# AIRZAI_LED_SENSE_FLEX_REVA.net
KiCad netlist of a schematic drawn in Altium Designer
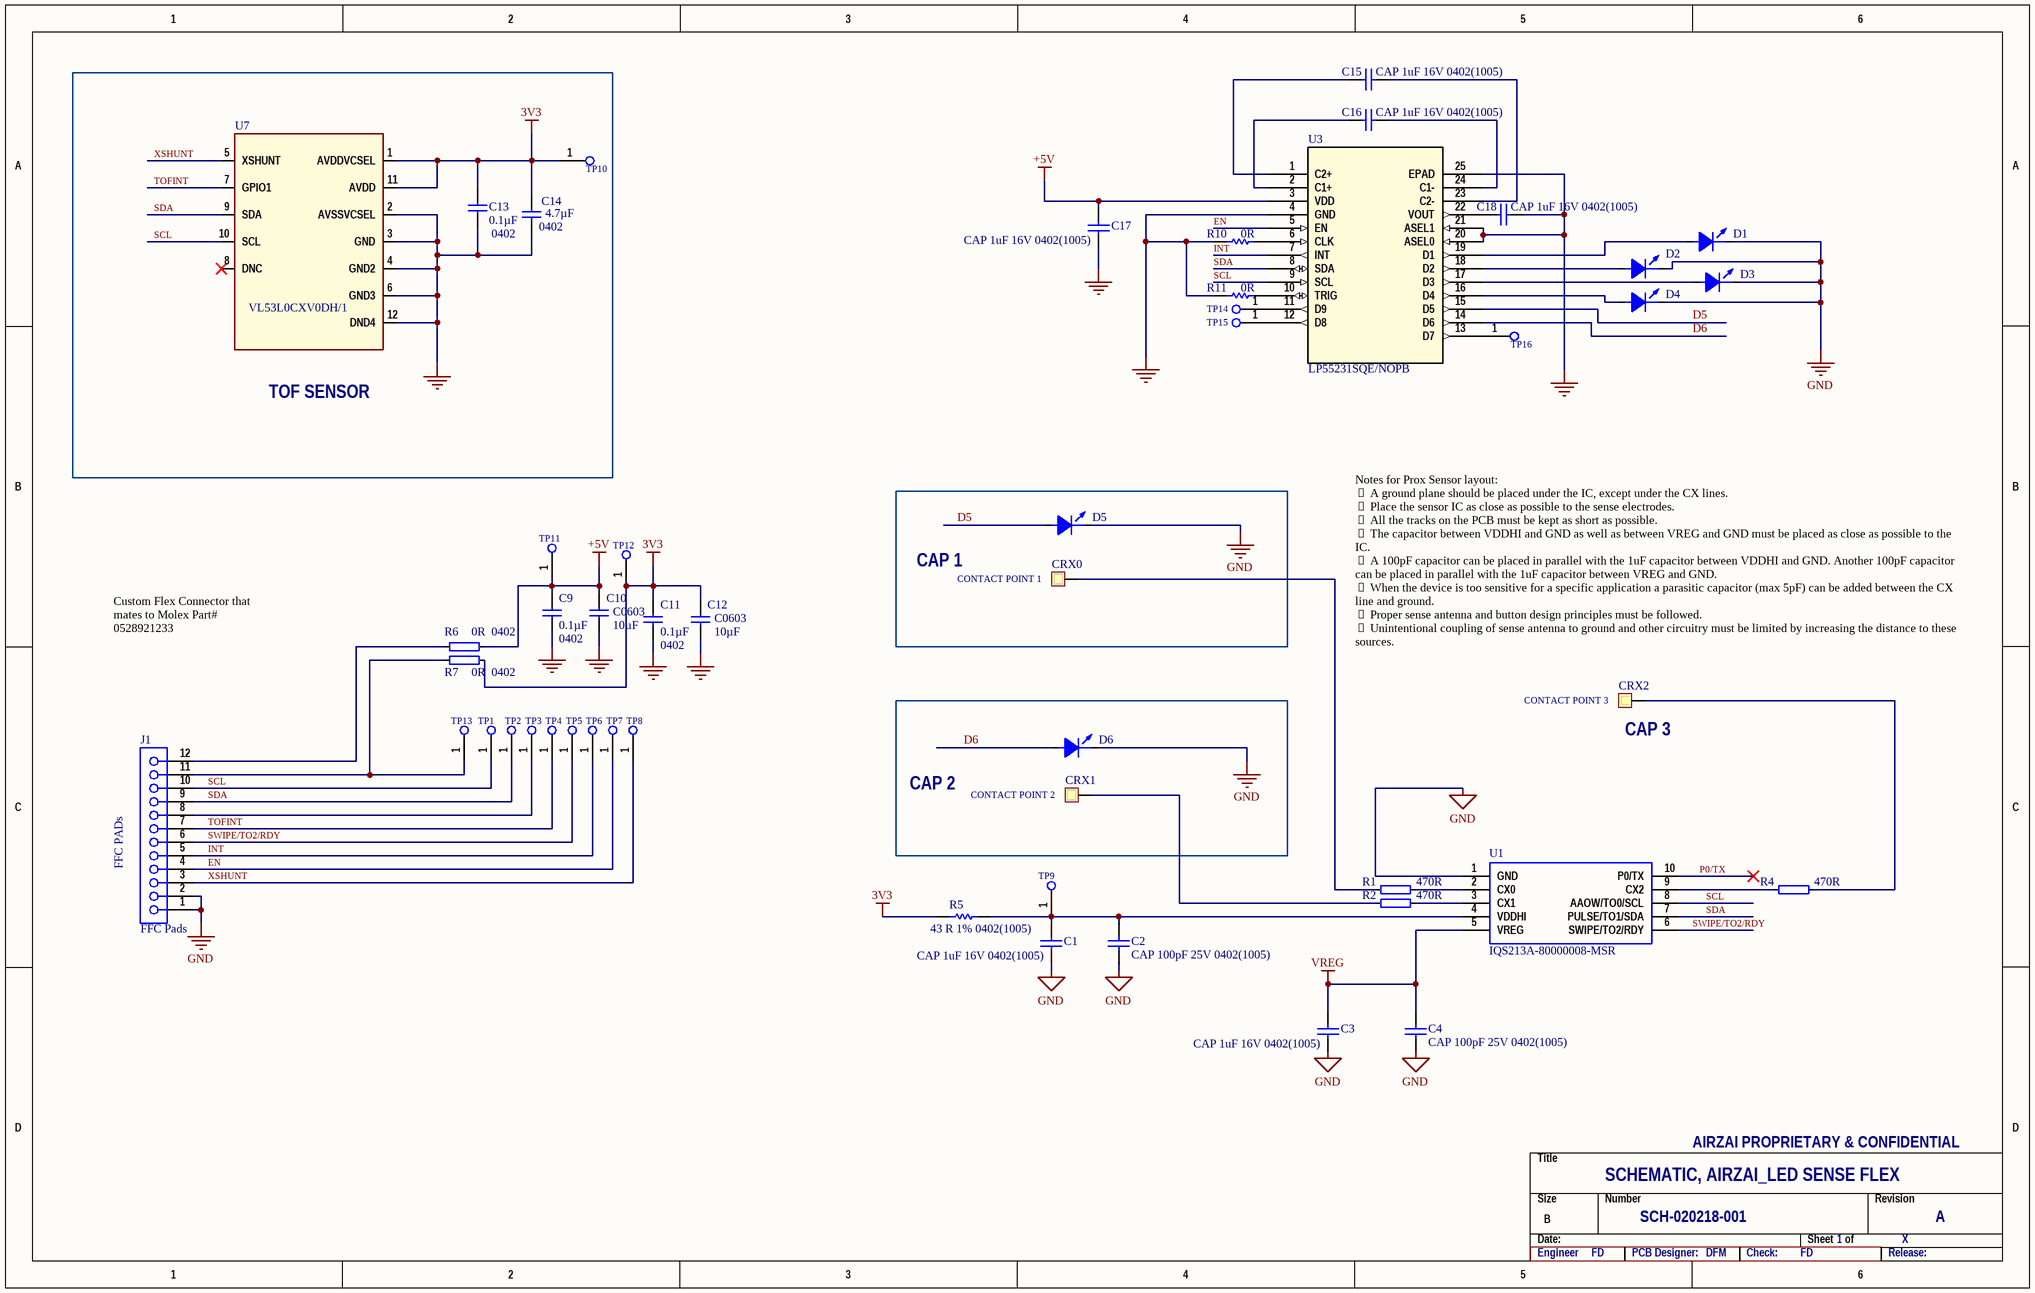
[diagram p0: AIRZAI_LED_SENSE_FLEX_REVA.SchDoc]

(export (version "E")
  (design (tool "Eeschema 10.0.6"))
  (components
    (comp (ref "C1")
      (value "CAP 1uF 16V 0402(1005)")
      (footprint "0402-A")
      (description "CAP 1uF 16V ±10% 0402 (1005 Metric) Thickness 0.6mm SMD")
      (fields (field (name "TOLERANCE") "Â±10%") (field (name "MANUFACTURER") "Taiyo Yuden"))
      (libsource (lib "AIRZAI_LED_SENSE_FLEX_REVA") (part "CAP"))
    )
    (comp (ref "C2")
      (value "CAP 100pF 25V 0402(1005)")
      (footprint "0402-A")
      (description "CAP 100pF 25V ±2% 0402 (1005 Metric) Thickness 0.6mm SMD")
      (fields (field (name "TOLERANCE") "Â±2%") (field (name "MANUFACTURER") "Yageo"))
      (libsource (lib "AIRZAI_LED_SENSE_FLEX_REVA") (part "CAP"))
    )
    (comp (ref "C3")
      (value "CAP 1uF 16V 0402(1005)")
      (footprint "0402-A")
      (description "CAP 1uF 16V ±10% 0402 (1005 Metric) Thickness 0.6mm SMD")
      (fields (field (name "TOLERANCE") "Â±10%") (field (name "MANUFACTURER") "Taiyo Yuden"))
      (libsource (lib "AIRZAI_LED_SENSE_FLEX_REVA") (part "CAP"))
    )
    (comp (ref "C4")
      (value "CAP 100pF 25V 0402(1005)")
      (footprint "0402-A")
      (description "CAP 100pF 25V ±2% 0402 (1005 Metric) Thickness 0.6mm SMD")
      (fields (field (name "TOLERANCE") "Â±2%") (field (name "MANUFACTURER") "Yageo"))
      (libsource (lib "AIRZAI_LED_SENSE_FLEX_REVA") (part "CAP"))
    )
    (comp (ref "C9")
      (value "0.1µF")
      (footprint "0402")
      (description "Capacitor, X7R, ±10%")
      (fields (field (name "MANUFACTURER") "TDK") (field (name "MANUFACTURER PART NUMBER") "C1005X7R1C104K"))
      (libsource (lib "Nordic Passive DB") (part "CAP"))
    )
    (comp (ref "C10")
      (value "10µF")
      (footprint "C0603")
      (description "Capacitor, X7R, ±10%")
      (fields
        (field (name "MANUFACTURER") "MURATA")
        (field (name "MANUFACTURER PART NUMBER") "GRM188R60J106ME47D")
      )
      (libsource (lib "Nordic Passive DB") (part "CAP"))
    )
    (comp (ref "C11")
      (value "0.1µF")
      (footprint "0402")
      (description "Capacitor, X7R, ±10%")
      (fields (field (name "MANUFACTURER") "TDK") (field (name "MANUFACTURER PART NUMBER") "C1005X7R1C104K"))
      (libsource (lib "Nordic Passive DB") (part "CAP"))
    )
    (comp (ref "C12")
      (value "10µF")
      (footprint "C0603")
      (description "Capacitor, X7R, ±10%")
      (fields
        (field (name "MANUFACTURER") "MURATA")
        (field (name "MANUFACTURER PART NUMBER") "GRM188R60J106ME47D")
      )
      (libsource (lib "Nordic Passive DB") (part "CAP"))
    )
    (comp (ref "C13")
      (value "0.1µF")
      (footprint "0402")
      (description "Capacitor, X7R, ±10%")
      (fields (field (name "MANUFACTURER") "TDK") (field (name "MANUFACTURER PART NUMBER") "C1005X7R1C104K"))
      (libsource (lib "Nordic Passive DB") (part "CAP"))
    )
    (comp (ref "C14")
      (value "4.7µF")
      (footprint "0402")
      (description "Capacitor, X7R, ±10%")
      (fields (field (name "MANUFACTURER") "TDK") (field (name "MANUFACTURER PART NUMBER") "C1005X5R0J475M"))
      (libsource (lib "Nordic Passive DB") (part "CAP"))
    )
    (comp (ref "C15")
      (value "CAP 1uF 16V 0402(1005)")
      (footprint "CAPC0402(1005)60_M")
      (description "CAP 1uF 16V ±10% 0402 (1005 Metric) Thickness 0.6mm SMD")
      (fields (field (name "TOLERANCE") "Â±10%") (field (name "MANUFACTURER") "Taiyo Yuden"))
      (libsource (lib "AIRZAI_LED_SENSE_FLEX_REVA") (part "CAP"))
    )
    (comp (ref "C16")
      (value "CAP 1uF 16V 0402(1005)")
      (footprint "CAPC0402(1005)60_M")
      (description "CAP 1uF 16V ±10% 0402 (1005 Metric) Thickness 0.6mm SMD")
      (fields (field (name "TOLERANCE") "Â±10%") (field (name "MANUFACTURER") "Taiyo Yuden"))
      (libsource (lib "AIRZAI_LED_SENSE_FLEX_REVA") (part "CAP"))
    )
    (comp (ref "C17")
      (value "CAP 1uF 16V 0402(1005)")
      (footprint "CAPC0402(1005)60_M")
      (description "CAP 1uF 16V ±10% 0402 (1005 Metric) Thickness 0.6mm SMD")
      (fields (field (name "TOLERANCE") "Â±10%") (field (name "MANUFACTURER") "Taiyo Yuden"))
      (libsource (lib "AIRZAI_LED_SENSE_FLEX_REVA") (part "CAP"))
    )
    (comp (ref "C18")
      (value "CAP 1uF 16V 0402(1005)")
      (footprint "CAPC0402(1005)60_M")
      (description "CAP 1uF 16V ±10% 0402 (1005 Metric) Thickness 0.6mm SMD")
      (fields (field (name "TOLERANCE") "Â±10%") (field (name "MANUFACTURER") "Taiyo Yuden"))
      (libsource (lib "AIRZAI_LED_SENSE_FLEX_REVA") (part "CAP"))
    )
    (comp (ref "CRX0")
      (value "CONTACT POINT 1")
      (footprint "CONTACT_POINT_1CM _SQ")
      (libsource (lib "AIRZAI_LED_SENSE_FLEX_REVA") (part "WIRE_POINT"))
    )
    (comp (ref "CRX1")
      (value "CONTACT POINT 2")
      (footprint "CONTACT_POINT_1CM _SQ")
      (libsource (lib "AIRZAI_LED_SENSE_FLEX_REVA") (part "WIRE_POINT"))
    )
    (comp (ref "CRX2")
      (value "CONTACT POINT 3")
      (footprint "CONTACT_POINT_0.7CM")
      (libsource (lib "AIRZAI_LED_SENSE_FLEX_REVA") (part "WIRE_POINT"))
    )
    (comp (ref "D1")
      (value "WHITE")
      (footprint "LED1206_LTW-C230DS")
      (fields (field (name "MANUFACTURER PART NUMBER") "LTW-C230DS") (field (name "MANUFACTURER") "LITEON"))
      (libsource (lib "AIRZAI_LED_SENSE_FLEX_REVA") (part "LED_LTW-C230DS"))
    )
    (comp (ref "D2")
      (value "WHITE")
      (footprint "LED1206_LTW-C230DS")
      (fields (field (name "MANUFACTURER PART NUMBER") "LTW-C230DS") (field (name "MANUFACTURER") "LITEON"))
      (libsource (lib "AIRZAI_LED_SENSE_FLEX_REVA") (part "LED_LTW-C230DS"))
    )
    (comp (ref "D3")
      (value "WHITE")
      (footprint "LED1206_LTW-C230DS")
      (fields (field (name "MANUFACTURER PART NUMBER") "LTW-C230DS") (field (name "MANUFACTURER") "LITEON"))
      (libsource (lib "AIRZAI_LED_SENSE_FLEX_REVA") (part "LED_LTW-C230DS"))
    )
    (comp (ref "D4")
      (value "WHITE")
      (footprint "LED1206_LTW-C230DS")
      (fields (field (name "MANUFACTURER PART NUMBER") "LTW-C230DS") (field (name "MANUFACTURER") "LITEON"))
      (libsource (lib "AIRZAI_LED_SENSE_FLEX_REVA") (part "LED_LTW-C230DS"))
    )
    (comp (ref "D5")
      (value "WHITE")
      (footprint "LED1206_LTW-C230DS")
      (fields (field (name "MANUFACTURER PART NUMBER") "LTW-C230DS") (field (name "MANUFACTURER") "LITEON"))
      (libsource (lib "AIRZAI_LED_SENSE_FLEX_REVA") (part "LED_LTW-C230DS"))
    )
    (comp (ref "D6")
      (value "WHITE")
      (footprint "LED1206_LTW-C230DS")
      (fields (field (name "MANUFACTURER PART NUMBER") "LTW-C230DS") (field (name "MANUFACTURER") "LITEON"))
      (libsource (lib "AIRZAI_LED_SENSE_FLEX_REVA") (part "LED_LTW-C230DS"))
    )
    (comp (ref "J1")
      (value "FFC Pads")
      (footprint "FFC_Pads")
      (description "0.5 mm Pitch FFC Pads")
      (libsource (lib "AIRZAI_LED_SENSE_FLEX_REVA") (part "FFC_PADS"))
    )
    (comp (ref "R1")
      (value "470R")
      (footprint "0402-A")
      (description "Resistor, ±1%, 0.063W")
      (fields
        (field (name "MANUFACTURER") "Panasonic")
        (field (name "MANUFACTURER PART NUMBER") "ERJ-2RKF4700X")
      )
      (libsource (lib "Nordic Passive DB") (part "RES_1"))
    )
    (comp (ref "R2")
      (value "470R")
      (footprint "0402-A")
      (description "Resistor, ±1%, 0.063W")
      (fields
        (field (name "MANUFACTURER") "Panasonic")
        (field (name "MANUFACTURER PART NUMBER") "ERJ-2RKF4700X")
      )
      (libsource (lib "Nordic Passive DB") (part "RES_1"))
    )
    (comp (ref "R4")
      (value "470R")
      (footprint "0402-A")
      (description "Resistor, ±1%, 0.063W")
      (fields
        (field (name "MANUFACTURER") "Panasonic")
        (field (name "MANUFACTURER PART NUMBER") "ERJ-2RKF4700X")
      )
      (libsource (lib "Nordic Passive DB") (part "RES_1"))
    )
    (comp (ref "R5")
      (value "43 R 1% 0402(1005)")
      (footprint "0402-A")
      (description "43R2 0.063W 1% 0402 (1005 Metric)  SMD")
      (fields (field (name "TOLERANCE") "1 %") (field (name "POWER") "0.063 W"))
      (libsource (lib "AIRZAI_LED_SENSE_FLEX_REVA") (part "RES"))
    )
    (comp (ref "R6")
      (value "0R")
      (footprint "0402")
      (description "Resistor, ±1%, 0.063W")
      (fields
        (field (name "MANUFACTURER") "Panasonic")
        (field (name "MANUFACTURER PART NUMBER") "ERJ-2GE0R00X")
      )
      (libsource (lib "Nordic Passive DB") (part "RES_1"))
    )
    (comp (ref "R7")
      (value "0R")
      (footprint "0402")
      (description "Resistor, ±1%, 0.063W")
      (fields
        (field (name "MANUFACTURER") "Panasonic")
        (field (name "MANUFACTURER PART NUMBER") "ERJ-2GE0R00X")
      )
      (libsource (lib "Nordic Passive DB") (part "RES_1"))
    )
    (comp (ref "R10")
      (value "0R")
      (footprint "0402")
      (description "Jumper 0402 (1005 Metric)")
      (fields (field (name "TOLERANCE") "None") (field (name "MANUFACTURER") "Panasonic"))
      (libsource (lib "AIRZAI_LED_SENSE_FLEX_REVA") (part "RES"))
    )
    (comp (ref "R11")
      (value "0R")
      (footprint "0402")
      (description "Jumper 0402 (1005 Metric)")
      (fields (field (name "TOLERANCE") "None") (field (name "MANUFACTURER") "Panasonic"))
      (libsource (lib "AIRZAI_LED_SENSE_FLEX_REVA") (part "RES"))
    )
    (comp (ref "TP1")
      (value "Test Point")
      (footprint "TP_0.9MM")
      (libsource (lib "AIRZAI_LED_SENSE_FLEX_REVA") (part "Test Point"))
    )
    (comp (ref "TP2")
      (value "Test Point")
      (footprint "TP_0.9MM")
      (libsource (lib "AIRZAI_LED_SENSE_FLEX_REVA") (part "Test Point"))
    )
    (comp (ref "TP3")
      (value "Test Point")
      (footprint "TP_0.9MM")
      (libsource (lib "AIRZAI_LED_SENSE_FLEX_REVA") (part "Test Point"))
    )
    (comp (ref "TP4")
      (value "Test Point")
      (footprint "TP_0.9MM")
      (libsource (lib "AIRZAI_LED_SENSE_FLEX_REVA") (part "Test Point"))
    )
    (comp (ref "TP5")
      (value "Test Point")
      (footprint "TP_0.9MM")
      (libsource (lib "AIRZAI_LED_SENSE_FLEX_REVA") (part "Test Point"))
    )
    (comp (ref "TP6")
      (value "Test Point")
      (footprint "TP_0.9MM")
      (libsource (lib "AIRZAI_LED_SENSE_FLEX_REVA") (part "Test Point"))
    )
    (comp (ref "TP7")
      (value "Test Point")
      (footprint "TP_0.9MM")
      (libsource (lib "AIRZAI_LED_SENSE_FLEX_REVA") (part "Test Point"))
    )
    (comp (ref "TP8")
      (value "Test Point")
      (footprint "TP_0.9MM")
      (libsource (lib "AIRZAI_LED_SENSE_FLEX_REVA") (part "Test Point"))
    )
    (comp (ref "TP9")
      (value "Test Point")
      (footprint "TP_0.9MM")
      (libsource (lib "AIRZAI_LED_SENSE_FLEX_REVA") (part "Test Point"))
    )
    (comp (ref "TP10")
      (value "Test Point")
      (footprint "TP_0.9MM")
      (libsource (lib "AIRZAI_LED_SENSE_FLEX_REVA") (part "Test Point"))
    )
    (comp (ref "TP11")
      (value "Test Point")
      (footprint "TP_0.9MM")
      (libsource (lib "AIRZAI_LED_SENSE_FLEX_REVA") (part "Test Point"))
    )
    (comp (ref "TP12")
      (value "Test Point")
      (footprint "TP_0.9MM")
      (libsource (lib "AIRZAI_LED_SENSE_FLEX_REVA") (part "Test Point"))
    )
    (comp (ref "TP13")
      (value "Test Point")
      (footprint "TP_0.9MM")
      (libsource (lib "AIRZAI_LED_SENSE_FLEX_REVA") (part "Test Point"))
    )
    (comp (ref "TP14")
      (value "Test Point")
      (footprint "TP_0.9MM")
      (libsource (lib "AIRZAI_LED_SENSE_FLEX_REVA") (part "Test Point"))
    )
    (comp (ref "TP15")
      (value "Test Point")
      (footprint "TP_0.9MM")
      (libsource (lib "AIRZAI_LED_SENSE_FLEX_REVA") (part "Test Point"))
    )
    (comp (ref "TP16")
      (value "Test Point")
      (footprint "TP_0.9MM")
      (libsource (lib "AIRZAI_LED_SENSE_FLEX_REVA") (part "Test Point"))
    )
    (comp (ref "U1")
      (value "IQS213A-80000008-MSR")
      (footprint "MSOP-10-IQS213A-80000008-MSR")
      (description "Capacitive Touch Sensors 3 Ch Capacitive Touch/Swipe Function")
      (fields
        (field (name "MANUFACTURER") "Azoteq")
        (field (name "MANUFACTURER PART NUMBER") "IQS213A-00000000-MSR")
      )
      (libsource (lib "IQS213A-80000008-MSR") (part "IQS213A-80000008-MSR"))
    )
    (comp (ref "U3")
      (value "LP55231SQE/NOPB")
      (footprint "WQFN-24-LP55231SQE/NOPB")
      (description "Imported")
      (fields (field (name "MANUFACTURER") "TI") (field (name "TOLERANCE") "None"))
      (libsource (lib "AltiumDesigner") (part "LP55231SQE/NOPB"))
    )
    (comp (ref "U7")
      (value "VL53L0CXV0DH/1")
      (footprint "VL53L0X")
      (fields (field (name "MANUFACTURER") "ST") (field (name "TOLERANCE") "None"))
      (libsource (lib "DFM_JBKEGSVS_Library") (part "VL53L0X"))
    )
  )
  (nets
    (net (code "1") (name "+5V") (class "Default")
      (node (ref "C10") (pin "1") (pinfunction "1_1") (pintype "passive"))
      (node (ref "C17") (pin "2") (pinfunction "2_2") (pintype "passive"))
      (node (ref "C9") (pin "1") (pinfunction "1_1") (pintype "passive"))
      (node (ref "R6") (pin "1") (pinfunction "1_1") (pintype "passive"))
      (node (ref "TP11") (pin "1") (pinfunction "1_1") (pintype "passive"))
      (node (ref "U3") (pin "3") (pinfunction "VDD_3") (pintype "power_in"))
    )
    (net (code "3") (name "/D5") (class "Default")
      (node (ref "D5") (pin "2") (pinfunction "ANODE_2") (pintype "passive"))
      (node (ref "U3") (pin "15") (pinfunction "D5_15") (pintype "output"))
    )
    (net (code "4") (name "/D6") (class "Default")
      (node (ref "D6") (pin "2") (pinfunction "ANODE_2") (pintype "passive"))
      (node (ref "U3") (pin "14") (pinfunction "D6_14") (pintype "output"))
    )
    (net (code "5") (name "/EN") (class "Default")
      (node (ref "J1") (pin "4") (pinfunction "4_4") (pintype "passive"))
      (node (ref "TP7") (pin "1") (pinfunction "1_1") (pintype "passive"))
      (node (ref "U3") (pin "5") (pinfunction "EN_5") (pintype "input"))
    )
    (net (code "6") (name "/INT") (class "Default")
      (node (ref "J1") (pin "5") (pinfunction "5_5") (pintype "passive"))
      (node (ref "TP6") (pin "1") (pinfunction "1_1") (pintype "passive"))
      (node (ref "U3") (pin "7") (pinfunction "INT_7") (pintype "output"))
    )
    (net (code "7") (name "/P0{slash}TX") (class "Default")
      (node (ref "U1") (pin "10") (pinfunction "P0/TX_10") (pintype "passive+no_connect"))
    )
    (net (code "8") (name "/SCL") (class "Default")
      (node (ref "J1") (pin "10") (pinfunction "10_10") (pintype "passive"))
      (node (ref "TP1") (pin "1") (pinfunction "1_1") (pintype "passive"))
      (node (ref "U1") (pin "8") (pinfunction "AAOW/TO0/SCL_8") (pintype "passive"))
      (node (ref "U3") (pin "9") (pinfunction "SCL_9") (pintype "input"))
      (node (ref "U7") (pin "10") (pinfunction "SCL_10") (pintype "passive"))
    )
    (net (code "9") (name "/SDA") (class "Default")
      (node (ref "J1") (pin "9") (pinfunction "9_9") (pintype "passive"))
      (node (ref "TP2") (pin "1") (pinfunction "1_1") (pintype "passive"))
      (node (ref "U1") (pin "7") (pinfunction "PULSE/TO1/SDA_7") (pintype "passive"))
      (node (ref "U3") (pin "8") (pinfunction "SDA_8") (pintype "bidirectional"))
      (node (ref "U7") (pin "9") (pinfunction "SDA_9") (pintype "passive"))
    )
    (net (code "10") (name "/SWIPE{slash}TO2{slash}RDY") (class "Default")
      (node (ref "J1") (pin "6") (pinfunction "6_6") (pintype "passive"))
      (node (ref "TP5") (pin "1") (pinfunction "1_1") (pintype "passive"))
      (node (ref "U1") (pin "6") (pinfunction "SWIPE/TO2/RDY_6") (pintype "passive"))
    )
    (net (code "11") (name "/TOFINT") (class "Default")
      (node (ref "J1") (pin "7") (pinfunction "7_7") (pintype "passive"))
      (node (ref "TP4") (pin "1") (pinfunction "1_1") (pintype "passive"))
      (node (ref "U7") (pin "7") (pinfunction "GPIO1_7") (pintype "passive"))
    )
    (net (code "12") (name "/XSHUNT") (class "Default")
      (node (ref "J1") (pin "3") (pinfunction "3_3") (pintype "passive"))
      (node (ref "TP8") (pin "1") (pinfunction "1_1") (pintype "passive"))
      (node (ref "U7") (pin "5") (pinfunction "XSHUNT_5") (pintype "passive"))
    )
    (net (code "13") (name "3V3") (class "Default")
      (node (ref "C11") (pin "1") (pinfunction "1_1") (pintype "passive"))
      (node (ref "C12") (pin "1") (pinfunction "1_1") (pintype "passive"))
      (node (ref "C13") (pin "1") (pinfunction "1_1") (pintype "passive"))
      (node (ref "C14") (pin "2") (pinfunction "2_2") (pintype "passive"))
      (node (ref "R5") (pin "1") (pinfunction "1_1") (pintype "passive"))
      (node (ref "R7") (pin "1") (pinfunction "1_1") (pintype "passive"))
      (node (ref "TP10") (pin "1") (pinfunction "1_1") (pintype "passive"))
      (node (ref "TP12") (pin "1") (pinfunction "1_1") (pintype "passive"))
      (node (ref "U7") (pin "1") (pinfunction "AVDDVCSEL_1") (pintype "passive"))
      (node (ref "U7") (pin "11") (pinfunction "AVDD_11") (pintype "passive"))
    )
    (net (code "14") (name "GND") (class "Default")
      (node (ref "C1") (pin "1") (pinfunction "1_1") (pintype "passive"))
      (node (ref "C10") (pin "2") (pinfunction "2_2") (pintype "passive"))
      (node (ref "C11") (pin "2") (pinfunction "2_2") (pintype "passive"))
      (node (ref "C12") (pin "2") (pinfunction "2_2") (pintype "passive"))
      (node (ref "C13") (pin "2") (pinfunction "2_2") (pintype "passive"))
      (node (ref "C14") (pin "1") (pinfunction "1_1") (pintype "passive"))
      (node (ref "C17") (pin "1") (pinfunction "1_1") (pintype "passive"))
      (node (ref "C18") (pin "2") (pinfunction "2_2") (pintype "passive"))
      (node (ref "C2") (pin "1") (pinfunction "1_1") (pintype "passive"))
      (node (ref "C3") (pin "1") (pinfunction "1_1") (pintype "passive"))
      (node (ref "C4") (pin "1") (pinfunction "1_1") (pintype "passive"))
      (node (ref "C9") (pin "2") (pinfunction "2_2") (pintype "passive"))
      (node (ref "D1") (pin "1") (pinfunction "CATHODE_1") (pintype "passive"))
      (node (ref "D2") (pin "1") (pinfunction "CATHODE_1") (pintype "passive"))
      (node (ref "D3") (pin "1") (pinfunction "CATHODE_1") (pintype "passive"))
      (node (ref "D4") (pin "1") (pinfunction "CATHODE_1") (pintype "passive"))
      (node (ref "D5") (pin "1") (pinfunction "CATHODE_1") (pintype "passive"))
      (node (ref "D6") (pin "1") (pinfunction "CATHODE_1") (pintype "passive"))
      (node (ref "J1") (pin "1") (pinfunction "1_1") (pintype "passive"))
      (node (ref "J1") (pin "2") (pinfunction "2_2") (pintype "passive"))
      (node (ref "R10") (pin "1") (pinfunction "1_1") (pintype "passive"))
      (node (ref "R11") (pin "1") (pinfunction "1_1") (pintype "passive"))
      (node (ref "U1") (pin "1") (pinfunction "GND_1") (pintype "passive"))
      (node (ref "U3") (pin "20") (pinfunction "ASEL0_20") (pintype "input"))
      (node (ref "U3") (pin "21") (pinfunction "ASEL1_21") (pintype "input"))
      (node (ref "U3") (pin "25") (pinfunction "EPAD_25") (pintype "passive"))
      (node (ref "U3") (pin "4") (pinfunction "GND_4") (pintype "power_in"))
      (node (ref "U7") (pin "12") (pinfunction "DND4_12") (pintype "passive"))
      (node (ref "U7") (pin "2") (pinfunction "AVSSVCSEL_2") (pintype "passive"))
      (node (ref "U7") (pin "3") (pinfunction "GND_3") (pintype "passive"))
      (node (ref "U7") (pin "4") (pinfunction "GND2_4") (pintype "passive"))
      (node (ref "U7") (pin "6") (pinfunction "GND3_6") (pintype "passive"))
    )
    (net (code "15") (name "Net-(CRX0-Pad1)") (class "Default")
      (node (ref "CRX0") (pin "1") (pinfunction "1_1") (pintype "passive"))
      (node (ref "R1") (pin "2") (pinfunction "2_2") (pintype "passive"))
    )
    (net (code "16") (name "Net-(CRX1-Pad1)") (class "Default")
      (node (ref "CRX1") (pin "1") (pinfunction "1_1") (pintype "passive"))
      (node (ref "R2") (pin "2") (pinfunction "2_2") (pintype "passive"))
    )
    (net (code "17") (name "Net-(CRX2-Pad1)") (class "Default")
      (node (ref "CRX2") (pin "1") (pinfunction "1_1") (pintype "passive"))
      (node (ref "R4") (pin "1") (pinfunction "1_1") (pintype "passive"))
    )
    (net (code "18") (name "Net-(D1-ANODE)") (class "Default")
      (node (ref "D1") (pin "2") (pinfunction "ANODE_2") (pintype "passive"))
      (node (ref "U3") (pin "19") (pinfunction "D1_19") (pintype "output"))
    )
    (net (code "19") (name "Net-(D2-ANODE)") (class "Default")
      (node (ref "D2") (pin "2") (pinfunction "ANODE_2") (pintype "passive"))
      (node (ref "U3") (pin "18") (pinfunction "D2_18") (pintype "output"))
    )
    (net (code "20") (name "Net-(D3-ANODE)") (class "Default")
      (node (ref "D3") (pin "2") (pinfunction "ANODE_2") (pintype "passive"))
      (node (ref "U3") (pin "17") (pinfunction "D3_17") (pintype "output"))
    )
    (net (code "21") (name "Net-(D4-ANODE)") (class "Default")
      (node (ref "D4") (pin "2") (pinfunction "ANODE_2") (pintype "passive"))
      (node (ref "U3") (pin "16") (pinfunction "D4_16") (pintype "output"))
    )
    (net (code "22") (name "Net-(J1-Pad8)") (class "Default")
      (node (ref "J1") (pin "8") (pinfunction "8_8") (pintype "passive"))
      (node (ref "TP3") (pin "1") (pinfunction "1_1") (pintype "passive"))
    )
    (net (code "23") (name "Net-(J1-Pad11)") (class "Default")
      (node (ref "J1") (pin "11") (pinfunction "11_11") (pintype "passive"))
      (node (ref "R7") (pin "2") (pinfunction "2_2") (pintype "passive"))
      (node (ref "TP13") (pin "1") (pinfunction "1_1") (pintype "passive"))
    )
    (net (code "24") (name "Net-(J1-Pad12)") (class "Default")
      (node (ref "J1") (pin "12") (pinfunction "12_12") (pintype "passive"))
      (node (ref "R6") (pin "2") (pinfunction "2_2") (pintype "passive"))
    )
    (net (code "25") (name "Net-(U1-CX0)") (class "Default")
      (node (ref "R1") (pin "1") (pinfunction "1_1") (pintype "passive"))
      (node (ref "U1") (pin "2") (pinfunction "CX0_2") (pintype "passive"))
    )
    (net (code "26") (name "Net-(U1-CX1)") (class "Default")
      (node (ref "R2") (pin "1") (pinfunction "1_1") (pintype "passive"))
      (node (ref "U1") (pin "3") (pinfunction "CX1_3") (pintype "passive"))
    )
    (net (code "27") (name "Net-(U1-CX2)") (class "Default")
      (node (ref "R4") (pin "2") (pinfunction "2_2") (pintype "passive"))
      (node (ref "U1") (pin "9") (pinfunction "CX2_9") (pintype "passive"))
    )
    (net (code "28") (name "Net-(U1-VDDHI)") (class "Default")
      (node (ref "C1") (pin "2") (pinfunction "2_2") (pintype "passive"))
      (node (ref "C2") (pin "2") (pinfunction "2_2") (pintype "passive"))
      (node (ref "R5") (pin "2") (pinfunction "2_2") (pintype "passive"))
      (node (ref "TP9") (pin "1") (pinfunction "1_1") (pintype "passive"))
      (node (ref "U1") (pin "4") (pinfunction "VDDHI_4") (pintype "passive"))
    )
    (net (code "29") (name "Net-(U3-C1+)") (class "Default")
      (node (ref "C16") (pin "1") (pinfunction "1_1") (pintype "passive"))
      (node (ref "U3") (pin "2") (pinfunction "C1+_2") (pintype "passive"))
    )
    (net (code "30") (name "Net-(U3-C1-)") (class "Default")
      (node (ref "C16") (pin "2") (pinfunction "2_2") (pintype "passive"))
      (node (ref "U3") (pin "24") (pinfunction "C1-_24") (pintype "passive"))
    )
    (net (code "31") (name "Net-(U3-C2+)") (class "Default")
      (node (ref "C15") (pin "1") (pinfunction "1_1") (pintype "passive"))
      (node (ref "U3") (pin "1") (pinfunction "C2+_1") (pintype "passive"))
    )
    (net (code "32") (name "Net-(U3-C2-)") (class "Default")
      (node (ref "C15") (pin "2") (pinfunction "2_2") (pintype "passive"))
      (node (ref "U3") (pin "23") (pinfunction "C2-_23") (pintype "passive"))
    )
    (net (code "33") (name "Net-(U3-CLK)") (class "Default")
      (node (ref "R10") (pin "2") (pinfunction "2_2") (pintype "passive"))
      (node (ref "U3") (pin "6") (pinfunction "CLK_6") (pintype "input"))
    )
    (net (code "34") (name "Net-(U3-D7)") (class "Default")
      (node (ref "TP16") (pin "1") (pinfunction "1_1") (pintype "passive"))
      (node (ref "U3") (pin "13") (pinfunction "D7_13") (pintype "output"))
    )
    (net (code "35") (name "Net-(U3-D8)") (class "Default")
      (node (ref "TP15") (pin "1") (pinfunction "1_1") (pintype "passive"))
      (node (ref "U3") (pin "12") (pinfunction "D8_12") (pintype "output"))
    )
    (net (code "36") (name "Net-(U3-D9)") (class "Default")
      (node (ref "TP14") (pin "1") (pinfunction "1_1") (pintype "passive"))
      (node (ref "U3") (pin "11") (pinfunction "D9_11") (pintype "output"))
    )
    (net (code "37") (name "Net-(U3-TRIG)") (class "Default")
      (node (ref "R11") (pin "2") (pinfunction "2_2") (pintype "passive"))
      (node (ref "U3") (pin "10") (pinfunction "TRIG_10") (pintype "bidirectional"))
    )
    (net (code "38") (name "Net-(U3-VOUT)") (class "Default")
      (node (ref "C18") (pin "1") (pinfunction "1_1") (pintype "passive"))
      (node (ref "U3") (pin "22") (pinfunction "VOUT_22") (pintype "output"))
    )
    (net (code "39") (name "VREG") (class "Default")
      (node (ref "C3") (pin "2") (pinfunction "2_2") (pintype "passive"))
      (node (ref "C4") (pin "2") (pinfunction "2_2") (pintype "passive"))
      (node (ref "U1") (pin "5") (pinfunction "VREG_5") (pintype "passive"))
    )
    (net (code "40") (name "unconnected-(U7-DNC-Pad8)") (class "Default")
      (node (ref "U7") (pin "8") (pinfunction "DNC_8") (pintype "passive+no_connect"))
    )
  )
)
